# dosimeter.net
KiCad netlist of a schematic drawn in EAGLE
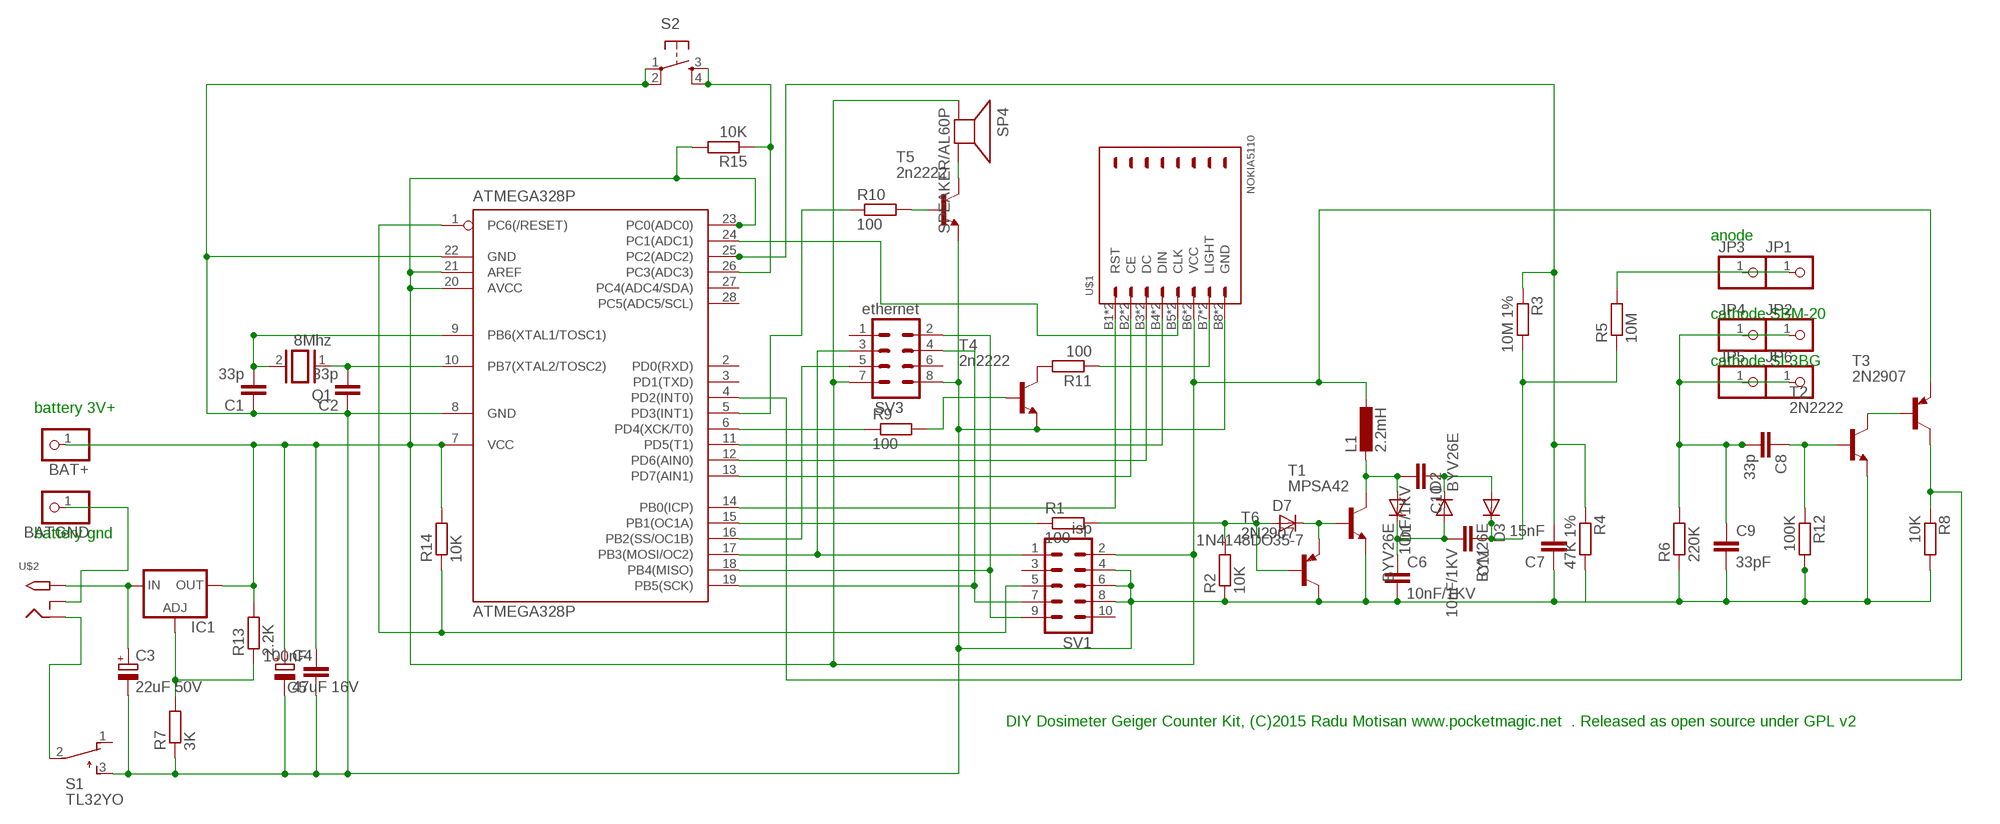
[diagram p0: schematic, sheet 1]

(export (version "E")
  (design (tool "Eeschema 10.0.6"))
  (components
    (comp (ref "ATMEGA328P")
      (value "ATMEGA328P")
      (footprint "eagle-import:DIL28-3")
      (libsource (lib "eagle-import") (part "MEGA8-P"))
    )
    (comp (ref "BAT+")
      (value "PINHD-1X1")
      (footprint "eagle-import:1X01")
      (libsource (lib "eagle-import") (part "PINHD-1X1"))
    )
    (comp (ref "BATGND")
      (value "PINHD-1X1")
      (footprint "eagle-import:1X01")
      (libsource (lib "eagle-import") (part "PINHD-1X1"))
    )
    (comp (ref "C1")
      (value "33p")
      (footprint "eagle-import:C2.5-2")
      (libsource (lib "eagle-import") (part "C2.5/2"))
    )
    (comp (ref "C2")
      (value "33p")
      (footprint "eagle-import:C2.5-2")
      (libsource (lib "eagle-import") (part "C2.5/2"))
    )
    (comp (ref "C3")
      (value "22uF 50V")
      (footprint "eagle-import:E2-5")
      (libsource (lib "eagle-import") (part "CPOL-EUE2-5"))
    )
    (comp (ref "C4")
      (value "47uF 16V")
      (footprint "eagle-import:E2-5")
      (libsource (lib "eagle-import") (part "CPOL-EUE2-5"))
    )
    (comp (ref "C5")
      (value "100nF")
      (footprint "eagle-import:C2.5-2")
      (libsource (lib "eagle-import") (part "C2.5/2"))
    )
    (comp (ref "C6")
      (value "10nF/1KV")
      (footprint "eagle-import:C5B3")
      (libsource (lib "eagle-import") (part "C5/3"))
    )
    (comp (ref "C7")
      (value "15nF")
      (footprint "eagle-import:C2.5-2")
      (libsource (lib "eagle-import") (part "C2.5/2"))
    )
    (comp (ref "C8")
      (value "33p")
      (footprint "eagle-import:C2.5-2")
      (libsource (lib "eagle-import") (part "C2.5/2"))
    )
    (comp (ref "C9")
      (value "33pF")
      (footprint "eagle-import:C2.5-2")
      (libsource (lib "eagle-import") (part "C2.5/2"))
    )
    (comp (ref "C10")
      (value "10nF/1KV")
      (footprint "eagle-import:C5B3")
      (libsource (lib "eagle-import") (part "C5/3"))
    )
    (comp (ref "C11")
      (value "10nF/1KV")
      (footprint "eagle-import:C5B3")
      (libsource (lib "eagle-import") (part "C5/3"))
    )
    (comp (ref "D1")
      (value "BYV26E")
      (footprint "eagle-import:D-7.5")
      (libsource (lib "eagle-import") (part "1N40047.5"))
    )
    (comp (ref "D2")
      (value "BYV26E")
      (footprint "eagle-import:D-7.5")
      (libsource (lib "eagle-import") (part "1N40047.5"))
    )
    (comp (ref "D3")
      (value "BYV26E")
      (footprint "eagle-import:D-7.5")
      (libsource (lib "eagle-import") (part "1N40047.5"))
    )
    (comp (ref "D7")
      (value "1N4148DO35-7")
      (footprint "eagle-import:DO35-7")
      (libsource (lib "eagle-import") (part "1N4148DO35-7"))
    )
    (comp (ref "IC1")
      (value "LM317TL")
      (footprint "eagle-import:317TL")
      (libsource (lib "eagle-import") (part "LM317TL"))
    )
    (comp (ref "JP1")
      (value "PINHD-1X1")
      (footprint "eagle-import:1X01")
      (libsource (lib "eagle-import") (part "PINHD-1X1"))
    )
    (comp (ref "JP2")
      (value "PINHD-1X1")
      (footprint "eagle-import:1X01")
      (libsource (lib "eagle-import") (part "PINHD-1X1"))
    )
    (comp (ref "JP3")
      (value "PINHD-1X1")
      (footprint "eagle-import:1X01")
      (libsource (lib "eagle-import") (part "PINHD-1X1"))
    )
    (comp (ref "JP4")
      (value "PINHD-1X1")
      (footprint "eagle-import:1X01")
      (libsource (lib "eagle-import") (part "PINHD-1X1"))
    )
    (comp (ref "JP5")
      (value "PINHD-1X1")
      (footprint "eagle-import:1X01")
      (libsource (lib "eagle-import") (part "PINHD-1X1"))
    )
    (comp (ref "JP6")
      (value "PINHD-1X1")
      (footprint "eagle-import:1X01")
      (libsource (lib "eagle-import") (part "PINHD-1X1"))
    )
    (comp (ref "L1")
      (value "2.2mH")
      (footprint "eagle-import:0207_10")
      (libsource (lib "eagle-import") (part "L-EU0207/10"))
    )
    (comp (ref "Q1")
      (value "8Mhz")
      (footprint "eagle-import:QS")
      (libsource (lib "eagle-import") (part "XTAL/S"))
    )
    (comp (ref "R1")
      (value "100")
      (footprint "eagle-import:0204_7")
      (libsource (lib "eagle-import") (part "R-EU_0204/7"))
    )
    (comp (ref "R2")
      (value "10K")
      (footprint "eagle-import:0204_7")
      (libsource (lib "eagle-import") (part "R-EU_0204/7"))
    )
    (comp (ref "R3")
      (value "10M 1%")
      (footprint "eagle-import:0204_7")
      (libsource (lib "eagle-import") (part "R-EU_0204/7"))
    )
    (comp (ref "R4")
      (value "47K 1%")
      (footprint "eagle-import:0204_7")
      (libsource (lib "eagle-import") (part "R-EU_0204/7"))
    )
    (comp (ref "R5")
      (value "10M")
      (footprint "eagle-import:0204_7")
      (libsource (lib "eagle-import") (part "R-EU_0204/7"))
    )
    (comp (ref "R6")
      (value "220K")
      (footprint "eagle-import:0204_7")
      (libsource (lib "eagle-import") (part "R-EU_0204/7"))
    )
    (comp (ref "R7")
      (value "3K")
      (footprint "eagle-import:0204_7")
      (libsource (lib "eagle-import") (part "R-EU_0204/7"))
    )
    (comp (ref "R8")
      (value "10K")
      (footprint "eagle-import:0204_7")
      (libsource (lib "eagle-import") (part "R-EU_0204/7"))
    )
    (comp (ref "R9")
      (value "100")
      (footprint "eagle-import:0204_7")
      (libsource (lib "eagle-import") (part "R-EU_0204/7"))
    )
    (comp (ref "R10")
      (value "100")
      (footprint "eagle-import:0204_7")
      (libsource (lib "eagle-import") (part "R-EU_0204/7"))
    )
    (comp (ref "R11")
      (value "100")
      (footprint "eagle-import:0204_7")
      (libsource (lib "eagle-import") (part "R-EU_0204/7"))
    )
    (comp (ref "R12")
      (value "100K")
      (footprint "eagle-import:0204_7")
      (libsource (lib "eagle-import") (part "R-EU_0204/7"))
    )
    (comp (ref "R13")
      (value "2.2K")
      (footprint "eagle-import:0204_7")
      (libsource (lib "eagle-import") (part "R-EU_0204/7"))
    )
    (comp (ref "R14")
      (value "10K")
      (footprint "eagle-import:0204_7")
      (libsource (lib "eagle-import") (part "R-EU_0204/7"))
    )
    (comp (ref "R15")
      (value "10K")
      (footprint "eagle-import:0204_7")
      (libsource (lib "eagle-import") (part "R-EU_0204/7"))
    )
    (comp (ref "S1")
      (value "TL32YO")
      (footprint "eagle-import:TL3XYO")
      (libsource (lib "eagle-import") (part "TL32YO"))
    )
    (comp (ref "S2")
      (value "TAC_SWITCHPTH")
      (footprint "eagle-import:TACTILE-PTH")
      (libsource (lib "eagle-import") (part "TAC_SWITCHPTH"))
    )
    (comp (ref "SP4")
      (value "SPEAKER/AL60P")
      (footprint "eagle-import:AL60P")
      (libsource (lib "eagle-import") (part "SPEAKER/AL60P"))
    )
    (comp (ref "SV1")
      (value "isp")
      (footprint "eagle-import:MA05-2")
      (libsource (lib "eagle-import") (part "MA05-2"))
    )
    (comp (ref "SV3")
      (value "ethernet")
      (footprint "eagle-import:MA04-2")
      (libsource (lib "eagle-import") (part "MA04-2"))
    )
    (comp (ref "T1")
      (value "MPSA42")
      (footprint "eagle-import:TO92-EBC-OVAL")
      (libsource (lib "eagle-import") (part "2N2222"))
    )
    (comp (ref "T2")
      (value "2N2222")
      (footprint "eagle-import:TO92-EBC-OVAL")
      (libsource (lib "eagle-import") (part "2N2222"))
    )
    (comp (ref "T3")
      (value "2N2907")
      (footprint "eagle-import:TO92-EBC-OVAL")
      (libsource (lib "eagle-import") (part "2N2907"))
    )
    (comp (ref "T4")
      (value "2n2222")
      (footprint "eagle-import:TO92-EBC")
      (libsource (lib "eagle-import") (part "-NPN-TO92-EBC2N2222"))
    )
    (comp (ref "T5")
      (value "2n2222")
      (footprint "eagle-import:TO92-EBC")
      (libsource (lib "eagle-import") (part "-NPN-TO92-EBC2N2222"))
    )
    (comp (ref "T6")
      (value "2N2907")
      (footprint "eagle-import:TO92-EBC-OVAL")
      (libsource (lib "eagle-import") (part "2N2907"))
    )
    (comp (ref "U$1")
      (value "NOKIA5110")
      (footprint "eagle-import:NOKIA5110")
      (libsource (lib "eagle-import") (part "NOKIA5110"))
    )
    (comp (ref "U$2")
      (value "2.1MMJACKTHM")
      (footprint "eagle-import:PJ-102A")
      (libsource (lib "eagle-import") (part "2.1MMJACKTHM"))
    )
  )
  (nets
    (net (code "1") (name "Net-(ATMEGA328P-AREF)") (class "Default")
      (node (ref "ATMEGA328P") (pin "20") (pinfunction "AVCC_20") (pintype "power_in"))
      (node (ref "ATMEGA328P") (pin "21") (pinfunction "AREF_21") (pintype "passive"))
      (node (ref "ATMEGA328P") (pin "23") (pinfunction "PC0(ADC0)_23") (pintype "bidirectional"))
      (node (ref "ATMEGA328P") (pin "7") (pinfunction "VCC_7") (pintype "power_in"))
      (node (ref "BAT+") (pin "1") (pinfunction "1_1") (pintype "passive"))
      (node (ref "C4") (pin "+") (pinfunction "+_+") (pintype "passive"))
      (node (ref "C5") (pin "2") (pinfunction "2_2") (pintype "passive"))
      (node (ref "IC1") (pin "2") (pinfunction "OUT_2") (pintype "passive"))
      (node (ref "L1") (pin "1") (pinfunction "1_1") (pintype "passive"))
      (node (ref "R13") (pin "2") (pinfunction "2_2") (pintype "passive"))
      (node (ref "R14") (pin "2") (pinfunction "2_2") (pintype "passive"))
      (node (ref "R15") (pin "2") (pinfunction "2_2") (pintype "passive"))
      (node (ref "SP4") (pin "1") (pinfunction "+_1") (pintype "passive"))
      (node (ref "SV1") (pin "2") (pinfunction "2_2") (pintype "passive"))
      (node (ref "SV3") (pin "7") (pinfunction "7_7") (pintype "passive"))
      (node (ref "T3") (pin "E") (pinfunction "E_E") (pintype "passive"))
      (node (ref "U$1") (pin "B6") (pinfunction "VCC_B6") (pintype "bidirectional"))
      (node (ref "U$1") (pin "T6") (pinfunction "VCC_T6") (pintype "bidirectional"))
    )
    (net (code "2") (name "Net-(ATMEGA328P-PB0(ICP))") (class "Default")
      (node (ref "ATMEGA328P") (pin "14") (pinfunction "PB0(ICP)_14") (pintype "bidirectional"))
      (node (ref "U$1") (pin "B1") (pinfunction "RST_B1") (pintype "bidirectional"))
      (node (ref "U$1") (pin "T1") (pinfunction "RST_T1") (pintype "bidirectional"))
    )
    (net (code "3") (name "Net-(ATMEGA328P-PB1(OC1A))") (class "Default")
      (node (ref "ATMEGA328P") (pin "15") (pinfunction "PB1(OC1A)_15") (pintype "bidirectional"))
      (node (ref "R1") (pin "1") (pinfunction "1_1") (pintype "passive"))
    )
    (net (code "4") (name "Net-(ATMEGA328P-PB2(SS{slash}OC1B))") (class "Default")
      (node (ref "ATMEGA328P") (pin "16") (pinfunction "PB2(SS/OC1B)_16") (pintype "bidirectional"))
      (node (ref "SV3") (pin "5") (pinfunction "5_5") (pintype "passive"))
    )
    (net (code "5") (name "Net-(ATMEGA328P-PB3(MOSI{slash}OC2))") (class "Default")
      (node (ref "ATMEGA328P") (pin "17") (pinfunction "PB3(MOSI/OC2)_17") (pintype "bidirectional"))
      (node (ref "SV1") (pin "1") (pinfunction "1_1") (pintype "passive"))
      (node (ref "SV3") (pin "3") (pinfunction "3_3") (pintype "passive"))
    )
    (net (code "6") (name "Net-(ATMEGA328P-PB4(MISO))") (class "Default")
      (node (ref "ATMEGA328P") (pin "18") (pinfunction "PB4(MISO)_18") (pintype "bidirectional"))
      (node (ref "SV1") (pin "9") (pinfunction "9_9") (pintype "passive"))
      (node (ref "SV3") (pin "2") (pinfunction "2_2") (pintype "passive"))
    )
    (net (code "7") (name "Net-(ATMEGA328P-PB5(SCK))") (class "Default")
      (node (ref "ATMEGA328P") (pin "19") (pinfunction "PB5(SCK)_19") (pintype "bidirectional"))
      (node (ref "SV1") (pin "7") (pinfunction "7_7") (pintype "passive"))
      (node (ref "SV3") (pin "4") (pinfunction "4_4") (pintype "passive"))
    )
    (net (code "8") (name "Net-(ATMEGA328P-PB6(XTAL1{slash}TOSC1))") (class "Default")
      (node (ref "ATMEGA328P") (pin "9") (pinfunction "PB6(XTAL1/TOSC1)_9") (pintype "bidirectional"))
      (node (ref "C1") (pin "2") (pinfunction "2_2") (pintype "passive"))
      (node (ref "Q1") (pin "2") (pinfunction "2_2") (pintype "passive"))
    )
    (net (code "9") (name "Net-(ATMEGA328P-PB7(XTAL2{slash}TOSC2))") (class "Default")
      (node (ref "ATMEGA328P") (pin "10") (pinfunction "PB7(XTAL2/TOSC2)_10") (pintype "bidirectional"))
      (node (ref "C2") (pin "2") (pinfunction "2_2") (pintype "passive"))
      (node (ref "Q1") (pin "1") (pinfunction "1_1") (pintype "passive"))
    )
    (net (code "10") (name "Net-(ATMEGA328P-PC1(ADC1))") (class "Default")
      (node (ref "ATMEGA328P") (pin "24") (pinfunction "PC1(ADC1)_24") (pintype "bidirectional"))
      (node (ref "U$1") (pin "B5") (pinfunction "CLK_B5") (pintype "bidirectional"))
      (node (ref "U$1") (pin "T5") (pinfunction "CLK_T5") (pintype "bidirectional"))
    )
    (net (code "11") (name "Net-(ATMEGA328P-PC2(ADC2))") (class "Default")
      (node (ref "ATMEGA328P") (pin "25") (pinfunction "PC2(ADC2)_25") (pintype "bidirectional"))
      (node (ref "C7") (pin "2") (pinfunction "2_2") (pintype "passive"))
      (node (ref "R3") (pin "1") (pinfunction "1_1") (pintype "passive"))
      (node (ref "R4") (pin "1") (pinfunction "1_1") (pintype "passive"))
    )
    (net (code "12") (name "Net-(ATMEGA328P-PC3(ADC3))") (class "Default")
      (node (ref "ATMEGA328P") (pin "26") (pinfunction "PC3(ADC3)_26") (pintype "bidirectional"))
      (node (ref "R15") (pin "1") (pinfunction "1_1") (pintype "passive"))
      (node (ref "S2") (pin "3") (pinfunction "3_3") (pintype "passive"))
      (node (ref "S2") (pin "4") (pinfunction "4_4") (pintype "passive"))
    )
    (net (code "13") (name "Net-(ATMEGA328P-PC6({slash}RESET))") (class "Default")
      (node (ref "ATMEGA328P") (pin "1") (pinfunction "PC6(/RESET)_1") (pintype "bidirectional"))
      (node (ref "R14") (pin "1") (pinfunction "1_1") (pintype "passive"))
      (node (ref "SV1") (pin "5") (pinfunction "5_5") (pintype "passive"))
    )
    (net (code "14") (name "Net-(ATMEGA328P-PD2(INT0))") (class "Default")
      (node (ref "ATMEGA328P") (pin "4") (pinfunction "PD2(INT0)_4") (pintype "bidirectional"))
      (node (ref "R8") (pin "1") (pinfunction "1_1") (pintype "passive"))
      (node (ref "T3") (pin "C") (pinfunction "C_C") (pintype "passive"))
    )
    (net (code "15") (name "Net-(ATMEGA328P-PD3(INT1))") (class "Default")
      (node (ref "ATMEGA328P") (pin "5") (pinfunction "PD3(INT1)_5") (pintype "bidirectional"))
      (node (ref "R10") (pin "1") (pinfunction "1_1") (pintype "passive"))
    )
    (net (code "16") (name "Net-(ATMEGA328P-PD4(XCK{slash}T0))") (class "Default")
      (node (ref "ATMEGA328P") (pin "6") (pinfunction "PD4(XCK/T0)_6") (pintype "bidirectional"))
      (node (ref "R9") (pin "1") (pinfunction "1_1") (pintype "passive"))
    )
    (net (code "17") (name "Net-(ATMEGA328P-PD5(T1))") (class "Default")
      (node (ref "ATMEGA328P") (pin "11") (pinfunction "PD5(T1)_11") (pintype "bidirectional"))
      (node (ref "U$1") (pin "B4") (pinfunction "DIN_B4") (pintype "bidirectional"))
      (node (ref "U$1") (pin "T4") (pinfunction "DIN_T4") (pintype "bidirectional"))
    )
    (net (code "18") (name "Net-(ATMEGA328P-PD6(AIN0))") (class "Default")
      (node (ref "ATMEGA328P") (pin "12") (pinfunction "PD6(AIN0)_12") (pintype "bidirectional"))
      (node (ref "U$1") (pin "B3") (pinfunction "DC_B3") (pintype "bidirectional"))
      (node (ref "U$1") (pin "T3") (pinfunction "DC_T3") (pintype "bidirectional"))
    )
    (net (code "19") (name "Net-(ATMEGA328P-PD7(AIN1))") (class "Default")
      (node (ref "ATMEGA328P") (pin "13") (pinfunction "PD7(AIN1)_13") (pintype "bidirectional"))
      (node (ref "U$1") (pin "B2") (pinfunction "CE_B2") (pintype "bidirectional"))
      (node (ref "U$1") (pin "T2") (pinfunction "CE_T2") (pintype "bidirectional"))
    )
    (net (code "20") (name "Net-(BATGND-Pad1)") (class "Default")
      (node (ref "BATGND") (pin "1") (pinfunction "1_1") (pintype "passive"))
      (node (ref "U$2") (pin "RING_SW") (pinfunction "RING_SW_RING_SW") (pintype "bidirectional"))
    )
    (net (code "21") (name "Net-(C8-Pad1)") (class "Default")
      (node (ref "C8") (pin "1") (pinfunction "1_1") (pintype "passive"))
      (node (ref "R12") (pin "1") (pinfunction "1_1") (pintype "passive"))
      (node (ref "T2") (pin "B") (pinfunction "B_B") (pintype "passive"))
    )
    (net (code "22") (name "Net-(C8-Pad2)") (class "Default")
      (node (ref "C8") (pin "2") (pinfunction "2_2") (pintype "passive"))
      (node (ref "C9") (pin "1") (pinfunction "1_1") (pintype "passive"))
      (node (ref "JP2") (pin "1") (pinfunction "1_1") (pintype "passive"))
      (node (ref "JP4") (pin "1") (pinfunction "1_1") (pintype "passive"))
      (node (ref "JP5") (pin "1") (pinfunction "1_1") (pintype "passive"))
      (node (ref "JP6") (pin "1") (pinfunction "1_1") (pintype "passive"))
      (node (ref "R6") (pin "2") (pinfunction "2_2") (pintype "passive"))
    )
    (net (code "23") (name "Net-(C10-Pad1)") (class "Default")
      (node (ref "C10") (pin "1") (pinfunction "1_1") (pintype "passive"))
      (node (ref "D2") (pin "C") (pinfunction "C_C") (pintype "passive"))
      (node (ref "D3") (pin "A") (pinfunction "A_A") (pintype "passive"))
    )
    (net (code "24") (name "Net-(C10-Pad2)") (class "Default")
      (node (ref "C10") (pin "2") (pinfunction "2_2") (pintype "passive"))
      (node (ref "D1") (pin "A") (pinfunction "A_A") (pintype "passive"))
      (node (ref "L1") (pin "2") (pinfunction "2_2") (pintype "passive"))
      (node (ref "T1") (pin "C") (pinfunction "C_C") (pintype "passive"))
    )
    (net (code "25") (name "Net-(C11-Pad1)") (class "Default")
      (node (ref "C11") (pin "1") (pinfunction "1_1") (pintype "passive"))
      (node (ref "D3") (pin "C") (pinfunction "C_C") (pintype "passive"))
      (node (ref "R3") (pin "2") (pinfunction "2_2") (pintype "passive"))
      (node (ref "R5") (pin "1") (pinfunction "1_1") (pintype "passive"))
    )
    (net (code "26") (name "Net-(C11-Pad2)") (class "Default")
      (node (ref "C11") (pin "2") (pinfunction "2_2") (pintype "passive"))
      (node (ref "C6") (pin "1") (pinfunction "1_1") (pintype "passive"))
      (node (ref "D1") (pin "C") (pinfunction "C_C") (pintype "passive"))
      (node (ref "D2") (pin "A") (pinfunction "A_A") (pintype "passive"))
    )
    (net (code "27") (name "Net-(D7-PadA)") (class "Default")
      (node (ref "D7") (pin "A") (pinfunction "A_A") (pintype "passive"))
      (node (ref "R1") (pin "2") (pinfunction "2_2") (pintype "passive"))
      (node (ref "R2") (pin "2") (pinfunction "2_2") (pintype "passive"))
      (node (ref "T6") (pin "B") (pinfunction "B_B") (pintype "passive"))
    )
    (net (code "28") (name "Net-(D7-PadC)") (class "Default")
      (node (ref "D7") (pin "C") (pinfunction "C_C") (pintype "passive"))
      (node (ref "T1") (pin "B") (pinfunction "B_B") (pintype "passive"))
      (node (ref "T6") (pin "E") (pinfunction "E_E") (pintype "passive"))
    )
    (net (code "29") (name "Net-(IC1-ADJ)") (class "Default")
      (node (ref "IC1") (pin "1") (pinfunction "ADJ_1") (pintype "input"))
      (node (ref "R13") (pin "1") (pinfunction "1_1") (pintype "passive"))
      (node (ref "R7") (pin "2") (pinfunction "2_2") (pintype "passive"))
    )
    (net (code "30") (name "Net-(IC1-IN)") (class "Default")
      (node (ref "C3") (pin "+") (pinfunction "+_+") (pintype "passive"))
      (node (ref "IC1") (pin "3") (pinfunction "IN_3") (pintype "input"))
      (node (ref "U$2") (pin "TIP") (pinfunction "TIP_TIP") (pintype "bidirectional"))
    )
    (net (code "31") (name "Net-(JP1-Pad1)") (class "Default")
      (node (ref "JP1") (pin "1") (pinfunction "1_1") (pintype "passive"))
      (node (ref "JP3") (pin "1") (pinfunction "1_1") (pintype "passive"))
      (node (ref "R5") (pin "2") (pinfunction "2_2") (pintype "passive"))
    )
    (net (code "32") (name "Net-(R9-Pad2)") (class "Default")
      (node (ref "R9") (pin "2") (pinfunction "2_2") (pintype "passive"))
      (node (ref "T4") (pin "B") (pinfunction "B_B") (pintype "passive"))
    )
    (net (code "33") (name "Net-(R10-Pad2)") (class "Default")
      (node (ref "R10") (pin "2") (pinfunction "2_2") (pintype "passive"))
      (node (ref "T5") (pin "B") (pinfunction "B_B") (pintype "passive"))
    )
    (net (code "34") (name "Net-(R11-Pad1)") (class "Default")
      (node (ref "R11") (pin "1") (pinfunction "1_1") (pintype "passive"))
      (node (ref "U$1") (pin "B7") (pinfunction "LIGHT_B7") (pintype "bidirectional"))
      (node (ref "U$1") (pin "T7") (pinfunction "LIGHT_T7") (pintype "bidirectional"))
    )
    (net (code "35") (name "Net-(R11-Pad2)") (class "Default")
      (node (ref "R11") (pin "2") (pinfunction "2_2") (pintype "passive"))
      (node (ref "T4") (pin "C") (pinfunction "C_C") (pintype "passive"))
    )
    (net (code "36") (name "Net-(S1-P)") (class "Default")
      (node (ref "S1") (pin "2") (pinfunction "P_2") (pintype "passive"))
      (node (ref "U$2") (pin "RING") (pinfunction "RING_RING") (pintype "bidirectional"))
    )
    (net (code "37") (name "Net-(S1-S)") (class "Default")
      (node (ref "ATMEGA328P") (pin "22") (pinfunction "GND_22") (pintype "power_in"))
      (node (ref "ATMEGA328P") (pin "8") (pinfunction "GND_8") (pintype "power_in"))
      (node (ref "C1") (pin "1") (pinfunction "1_1") (pintype "passive"))
      (node (ref "C2") (pin "1") (pinfunction "1_1") (pintype "passive"))
      (node (ref "C3") (pin "-") (pinfunction "-_-") (pintype "passive"))
      (node (ref "C4") (pin "-") (pinfunction "-_-") (pintype "passive"))
      (node (ref "C5") (pin "1") (pinfunction "1_1") (pintype "passive"))
      (node (ref "C6") (pin "2") (pinfunction "2_2") (pintype "passive"))
      (node (ref "C7") (pin "1") (pinfunction "1_1") (pintype "passive"))
      (node (ref "C9") (pin "2") (pinfunction "2_2") (pintype "passive"))
      (node (ref "R12") (pin "2") (pinfunction "2_2") (pintype "passive"))
      (node (ref "R2") (pin "1") (pinfunction "1_1") (pintype "passive"))
      (node (ref "R4") (pin "2") (pinfunction "2_2") (pintype "passive"))
      (node (ref "R6") (pin "1") (pinfunction "1_1") (pintype "passive"))
      (node (ref "R7") (pin "1") (pinfunction "1_1") (pintype "passive"))
      (node (ref "R8") (pin "2") (pinfunction "2_2") (pintype "passive"))
      (node (ref "S1") (pin "3") (pinfunction "S_3") (pintype "passive"))
      (node (ref "S2") (pin "1") (pinfunction "1_1") (pintype "passive"))
      (node (ref "S2") (pin "2") (pinfunction "2_2") (pintype "passive"))
      (node (ref "SV1") (pin "4") (pinfunction "4_4") (pintype "passive"))
      (node (ref "SV1") (pin "6") (pinfunction "6_6") (pintype "passive"))
      (node (ref "SV1") (pin "8") (pinfunction "8_8") (pintype "passive"))
      (node (ref "SV3") (pin "8") (pinfunction "8_8") (pintype "passive"))
      (node (ref "T1") (pin "E") (pinfunction "E_E") (pintype "passive"))
      (node (ref "T2") (pin "E") (pinfunction "E_E") (pintype "passive"))
      (node (ref "T4") (pin "E") (pinfunction "E_E") (pintype "passive"))
      (node (ref "T5") (pin "E") (pinfunction "E_E") (pintype "passive"))
      (node (ref "T6") (pin "C") (pinfunction "C_C") (pintype "passive"))
      (node (ref "U$1") (pin "B8") (pinfunction "GND_B8") (pintype "bidirectional"))
      (node (ref "U$1") (pin "T8") (pinfunction "GND_T8") (pintype "bidirectional"))
    )
    (net (code "38") (name "Net-(SP4--)") (class "Default")
      (node (ref "SP4") (pin "2") (pinfunction "-_2") (pintype "passive"))
      (node (ref "T5") (pin "C") (pinfunction "C_C") (pintype "passive"))
    )
    (net (code "39") (name "Net-(T2-PadC)") (class "Default")
      (node (ref "T2") (pin "C") (pinfunction "C_C") (pintype "passive"))
      (node (ref "T3") (pin "B") (pinfunction "B_B") (pintype "passive"))
    )
    (net (code "40") (name "unconnected-(ATMEGA328P-PC4(ADC4{slash}SDA)-Pad27)") (class "Default")
      (node (ref "ATMEGA328P") (pin "27") (pinfunction "PC4(ADC4/SDA)_27") (pintype "bidirectional"))
    )
    (net (code "41") (name "unconnected-(ATMEGA328P-PC5(ADC5{slash}SCL)-Pad28)") (class "Default")
      (node (ref "ATMEGA328P") (pin "28") (pinfunction "PC5(ADC5/SCL)_28") (pintype "bidirectional"))
    )
    (net (code "42") (name "unconnected-(ATMEGA328P-PD0(RXD)-Pad2)") (class "Default")
      (node (ref "ATMEGA328P") (pin "2") (pinfunction "PD0(RXD)_2") (pintype "bidirectional"))
    )
    (net (code "43") (name "unconnected-(ATMEGA328P-PD1(TXD)-Pad3)") (class "Default")
      (node (ref "ATMEGA328P") (pin "3") (pinfunction "PD1(TXD)_3") (pintype "bidirectional"))
    )
    (net (code "44") (name "unconnected-(S1-O-Pad1)") (class "Default")
      (node (ref "S1") (pin "1") (pinfunction "O_1") (pintype "passive"))
    )
    (net (code "45") (name "unconnected-(SV1-Pad3)") (class "Default")
      (node (ref "SV1") (pin "3") (pinfunction "3_3") (pintype "passive"))
    )
    (net (code "46") (name "unconnected-(SV1-Pad10)") (class "Default")
      (node (ref "SV1") (pin "10") (pinfunction "10_10") (pintype "passive"))
    )
    (net (code "47") (name "unconnected-(SV3-Pad1)") (class "Default")
      (node (ref "SV3") (pin "1") (pinfunction "1_1") (pintype "passive"))
    )
    (net (code "48") (name "unconnected-(SV3-Pad6)") (class "Default")
      (node (ref "SV3") (pin "6") (pinfunction "6_6") (pintype "passive"))
    )
  )
)
